# Rover_v1_Overall.net
KiCad netlist of a schematic drawn in EAGLE
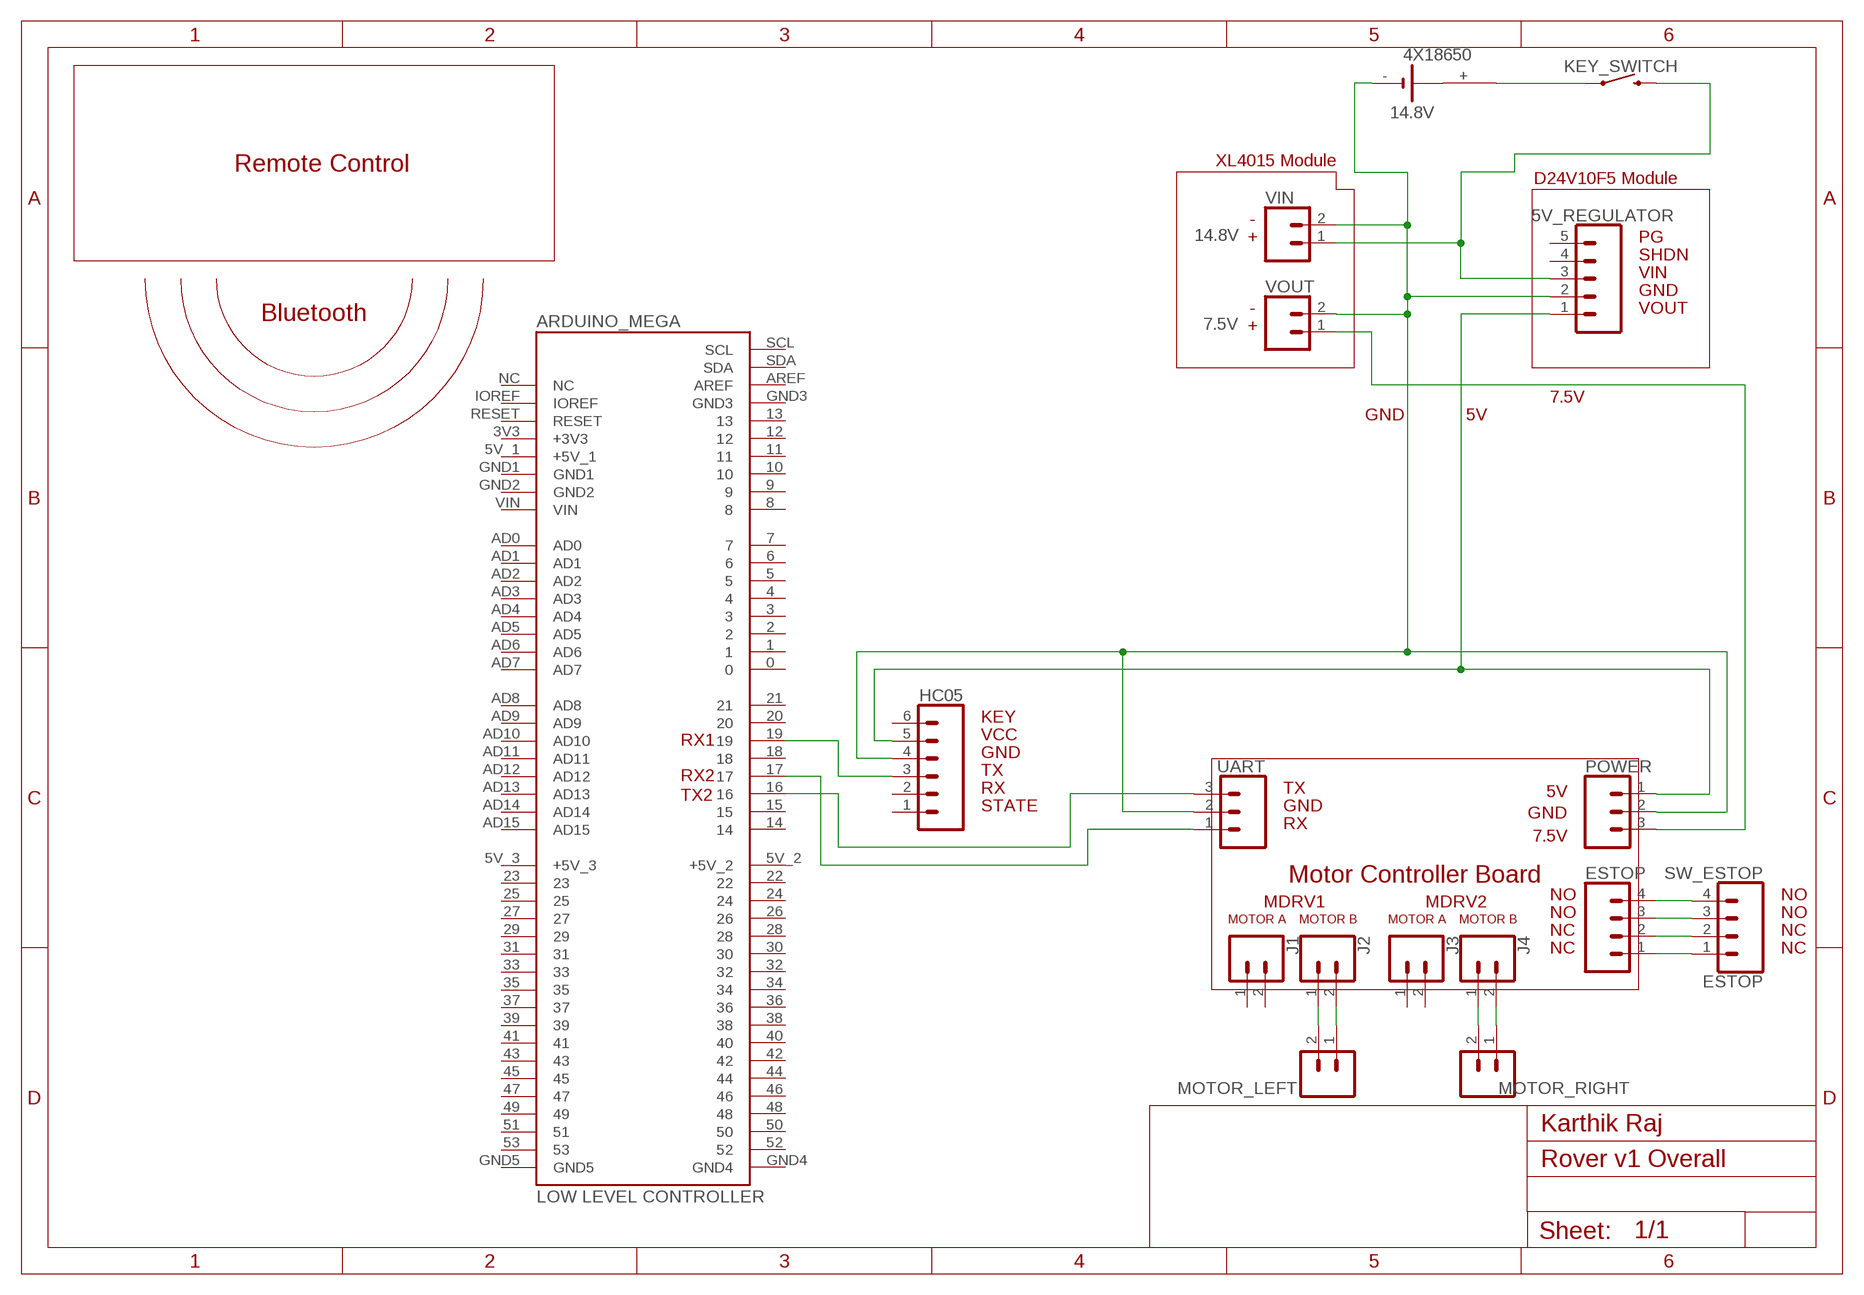
[diagram p0: schematic, sheet 1]

(export (version "E")
  (design (tool "Eeschema 10.0.6"))
  (components
    (comp (ref "4X18650")
      (value "14.8V")
      (footprint "eagle-import:B2430UNI")
      (libsource (lib "eagle-import") (part "B2430UNI"))
    )
    (comp (ref "5V_REGULATOR")
      (value "CONN_05")
      (footprint "eagle-import:1X05")
      (libsource (lib "eagle-import") (part "CONN_05"))
    )
    (comp (ref "ARDUINO_MEGA")
      (value "LOW LEVEL CONTROLLER")
      (footprint "eagle-import:ARDUINO_A000067")
      (fields (field (name "MF") "Arduino") (field (name "MP") "A000067"))
      (libsource (lib "eagle-import") (part "A000067"))
    )
    (comp (ref "ESTOP")
      (value "CONN_04PTH")
      (footprint "eagle-import:1X04")
      (libsource (lib "eagle-import") (part "CONN_04PTH"))
    )
    (comp (ref "HC05")
      (value "CONN_06SILK_FEMALE_PTH")
      (footprint "eagle-import:1X06")
      (libsource (lib "eagle-import") (part "CONN_06SILK_FEMALE_PTH"))
    )
    (comp (ref "J1")
      (value "CONN_02")
      (footprint "eagle-import:1X02")
      (libsource (lib "eagle-import") (part "CONN_02"))
    )
    (comp (ref "J2")
      (value "CONN_02")
      (footprint "eagle-import:1X02")
      (libsource (lib "eagle-import") (part "CONN_02"))
    )
    (comp (ref "J3")
      (value "CONN_02")
      (footprint "eagle-import:1X02")
      (libsource (lib "eagle-import") (part "CONN_02"))
    )
    (comp (ref "J4")
      (value "CONN_02")
      (footprint "eagle-import:1X02")
      (libsource (lib "eagle-import") (part "CONN_02"))
    )
    (comp (ref "KEY_SWITCH")
      (value "MOMENTARY-SWITCH-SPST-PTH-6.0MM")
      (footprint "eagle-import:TACTILE_SWITCH_PTH_6.0MM")
      (libsource (lib "eagle-import") (part "MOMENTARY-SWITCH-SPST-PTH-6.0MM"))
    )
    (comp (ref "MOTOR_LEFT")
      (value "CONN_02")
      (footprint "eagle-import:1X02")
      (libsource (lib "eagle-import") (part "CONN_02"))
    )
    (comp (ref "MOTOR_RIGHT")
      (value "CONN_02")
      (footprint "eagle-import:1X02")
      (libsource (lib "eagle-import") (part "CONN_02"))
    )
    (comp (ref "POWER")
      (value "CONN_03")
      (footprint "eagle-import:1X03")
      (libsource (lib "eagle-import") (part "CONN_03"))
    )
    (comp (ref "SW_ESTOP")
      (value "ESTOP")
      (footprint "eagle-import:1X04")
      (libsource (lib "eagle-import") (part "CONN_04PTH"))
    )
    (comp (ref "UART")
      (value "CONN_03")
      (footprint "eagle-import:1X03")
      (libsource (lib "eagle-import") (part "CONN_03"))
    )
    (comp (ref "VIN")
      (value "14.8V")
      (footprint "eagle-import:1X02")
      (libsource (lib "eagle-import") (part "CONN_02"))
    )
    (comp (ref "VOUT")
      (value "7.5V")
      (footprint "eagle-import:1X02")
      (libsource (lib "eagle-import") (part "CONN_02"))
    )
  )
  (nets
    (net (code "1") (name "Net-(4X18650-Pad+)") (class "Default")
      (node (ref "4X18650") (pin "+") (pinfunction "+_+") (pintype "passive"))
      (node (ref "KEY_SWITCH") (pin "1") (pinfunction "1_1") (pintype "passive"))
    )
    (net (code "2") (name "Net-(4X18650-Pad-)") (class "Default")
      (node (ref "4X18650") (pin "-") (pinfunction "-_-") (pintype "passive"))
      (node (ref "5V_REGULATOR") (pin "2") (pinfunction "2_2") (pintype "passive"))
      (node (ref "HC05") (pin "4") (pinfunction "4_4") (pintype "passive"))
      (node (ref "POWER") (pin "2") (pinfunction "2_2") (pintype "passive"))
      (node (ref "UART") (pin "2") (pinfunction "2_2") (pintype "passive"))
      (node (ref "VIN") (pin "2") (pinfunction "2_2") (pintype "passive"))
      (node (ref "VOUT") (pin "2") (pinfunction "2_2") (pintype "passive"))
    )
    (net (code "3") (name "Net-(5V_REGULATOR-Pad1)") (class "Default")
      (node (ref "5V_REGULATOR") (pin "1") (pinfunction "1_1") (pintype "passive"))
      (node (ref "HC05") (pin "5") (pinfunction "5_5") (pintype "passive"))
      (node (ref "POWER") (pin "1") (pinfunction "1_1") (pintype "passive"))
    )
    (net (code "4") (name "Net-(ARDUINO_MEGA-Pad16)") (class "Default")
      (node (ref "ARDUINO_MEGA") (pin "16") (pinfunction "16_16") (pintype "passive"))
      (node (ref "UART") (pin "3") (pinfunction "3_3") (pintype "passive"))
    )
    (net (code "5") (name "Net-(ARDUINO_MEGA-Pad17)") (class "Default")
      (node (ref "ARDUINO_MEGA") (pin "17") (pinfunction "17_17") (pintype "passive"))
      (node (ref "UART") (pin "1") (pinfunction "1_1") (pintype "passive"))
    )
    (net (code "6") (name "Net-(ARDUINO_MEGA-Pad19)") (class "Default")
      (node (ref "ARDUINO_MEGA") (pin "19") (pinfunction "19_19") (pintype "passive"))
      (node (ref "HC05") (pin "3") (pinfunction "3_3") (pintype "passive"))
    )
    (net (code "7") (name "Net-(ESTOP-Pad1)") (class "Default")
      (node (ref "ESTOP") (pin "1") (pinfunction "1_1") (pintype "passive"))
      (node (ref "SW_ESTOP") (pin "1") (pinfunction "1_1") (pintype "passive"))
    )
    (net (code "8") (name "Net-(ESTOP-Pad2)") (class "Default")
      (node (ref "ESTOP") (pin "2") (pinfunction "2_2") (pintype "passive"))
      (node (ref "SW_ESTOP") (pin "2") (pinfunction "2_2") (pintype "passive"))
    )
    (net (code "9") (name "Net-(ESTOP-Pad3)") (class "Default")
      (node (ref "ESTOP") (pin "3") (pinfunction "3_3") (pintype "passive"))
      (node (ref "SW_ESTOP") (pin "3") (pinfunction "3_3") (pintype "passive"))
    )
    (net (code "10") (name "Net-(ESTOP-Pad4)") (class "Default")
      (node (ref "ESTOP") (pin "4") (pinfunction "4_4") (pintype "passive"))
      (node (ref "SW_ESTOP") (pin "4") (pinfunction "4_4") (pintype "passive"))
    )
    (net (code "11") (name "Net-(J2-Pad1)") (class "Default")
      (node (ref "J2") (pin "1") (pinfunction "1_1") (pintype "passive"))
      (node (ref "MOTOR_LEFT") (pin "2") (pinfunction "2_2") (pintype "passive"))
    )
    (net (code "12") (name "Net-(J2-Pad2)") (class "Default")
      (node (ref "J2") (pin "2") (pinfunction "2_2") (pintype "passive"))
      (node (ref "MOTOR_LEFT") (pin "1") (pinfunction "1_1") (pintype "passive"))
    )
    (net (code "13") (name "Net-(J4-Pad1)") (class "Default")
      (node (ref "J4") (pin "1") (pinfunction "1_1") (pintype "passive"))
      (node (ref "MOTOR_RIGHT") (pin "2") (pinfunction "2_2") (pintype "passive"))
    )
    (net (code "14") (name "Net-(J4-Pad2)") (class "Default")
      (node (ref "J4") (pin "2") (pinfunction "2_2") (pintype "passive"))
      (node (ref "MOTOR_RIGHT") (pin "1") (pinfunction "1_1") (pintype "passive"))
    )
    (net (code "15") (name "Net-(KEY_SWITCH-2)") (class "Default")
      (node (ref "5V_REGULATOR") (pin "3") (pinfunction "3_3") (pintype "passive"))
      (node (ref "KEY_SWITCH") (pin "3") (pinfunction "2_3") (pintype "passive"))
      (node (ref "VIN") (pin "1") (pinfunction "1_1") (pintype "passive"))
    )
    (net (code "16") (name "Net-(POWER-Pad3)") (class "Default")
      (node (ref "POWER") (pin "3") (pinfunction "3_3") (pintype "passive"))
      (node (ref "VOUT") (pin "1") (pinfunction "1_1") (pintype "passive"))
    )
    (net (code "17") (name "unconnected-(4X18650-+-Pad+@1)") (class "Default")
      (node (ref "4X18650") (pin "+@1") (pinfunction "+_+@1") (pintype "passive"))
    )
    (net (code "18") (name "unconnected-(4X18650-+-Pad+@2)") (class "Default")
      (node (ref "4X18650") (pin "+@2") (pinfunction "+_+@2") (pintype "passive"))
    )
    (net (code "19") (name "unconnected-(4X18650-+-Pad+@3)") (class "Default")
      (node (ref "4X18650") (pin "+@3") (pinfunction "+_+@3") (pintype "passive"))
    )
    (net (code "20") (name "unconnected-(4X18650-+-Pad+@4)") (class "Default")
      (node (ref "4X18650") (pin "+@4") (pinfunction "+_+@4") (pintype "passive"))
    )
    (net (code "21") (name "unconnected-(4X18650---Pad-@1)") (class "Default")
      (node (ref "4X18650") (pin "-@1") (pinfunction "-_-@1") (pintype "passive"))
    )
    (net (code "22") (name "unconnected-(5V_REGULATOR-Pad4)") (class "Default")
      (node (ref "5V_REGULATOR") (pin "4") (pinfunction "4_4") (pintype "passive"))
    )
    (net (code "23") (name "unconnected-(5V_REGULATOR-Pad5)") (class "Default")
      (node (ref "5V_REGULATOR") (pin "5") (pinfunction "5_5") (pintype "passive"))
    )
    (net (code "24") (name "unconnected-(ARDUINO_MEGA-+3V3-Pad3V3)") (class "Default")
      (node (ref "ARDUINO_MEGA") (pin "3V3") (pinfunction "+3V3_3V3") (pintype "passive"))
    )
    (net (code "25") (name "unconnected-(ARDUINO_MEGA-+5V_1-Pad5V_1)") (class "Default")
      (node (ref "ARDUINO_MEGA") (pin "5V_1") (pinfunction "+5V_1_5V_1") (pintype "passive"))
    )
    (net (code "26") (name "unconnected-(ARDUINO_MEGA-+5V_2-Pad5V_2)") (class "Default")
      (node (ref "ARDUINO_MEGA") (pin "5V_2") (pinfunction "+5V_2_5V_2") (pintype "passive"))
    )
    (net (code "27") (name "unconnected-(ARDUINO_MEGA-+5V_3-Pad5V_3)") (class "Default")
      (node (ref "ARDUINO_MEGA") (pin "5V_3") (pinfunction "+5V_3_5V_3") (pintype "passive"))
    )
    (net (code "28") (name "unconnected-(ARDUINO_MEGA-Pad0)") (class "Default")
      (node (ref "ARDUINO_MEGA") (pin "0") (pinfunction "0_0") (pintype "passive"))
    )
    (net (code "29") (name "unconnected-(ARDUINO_MEGA-Pad1)") (class "Default")
      (node (ref "ARDUINO_MEGA") (pin "1") (pinfunction "1_1") (pintype "passive"))
    )
    (net (code "30") (name "unconnected-(ARDUINO_MEGA-Pad2)") (class "Default")
      (node (ref "ARDUINO_MEGA") (pin "2") (pinfunction "2_2") (pintype "passive"))
    )
    (net (code "31") (name "unconnected-(ARDUINO_MEGA-Pad3)") (class "Default")
      (node (ref "ARDUINO_MEGA") (pin "3") (pinfunction "3_3") (pintype "passive"))
    )
    (net (code "32") (name "unconnected-(ARDUINO_MEGA-Pad4)") (class "Default")
      (node (ref "ARDUINO_MEGA") (pin "4") (pinfunction "4_4") (pintype "passive"))
    )
    (net (code "33") (name "unconnected-(ARDUINO_MEGA-Pad5)") (class "Default")
      (node (ref "ARDUINO_MEGA") (pin "5") (pinfunction "5_5") (pintype "passive"))
    )
    (net (code "34") (name "unconnected-(ARDUINO_MEGA-Pad6)") (class "Default")
      (node (ref "ARDUINO_MEGA") (pin "6") (pinfunction "6_6") (pintype "passive"))
    )
    (net (code "35") (name "unconnected-(ARDUINO_MEGA-Pad7)") (class "Default")
      (node (ref "ARDUINO_MEGA") (pin "7") (pinfunction "7_7") (pintype "passive"))
    )
    (net (code "36") (name "unconnected-(ARDUINO_MEGA-Pad8)") (class "Default")
      (node (ref "ARDUINO_MEGA") (pin "8") (pinfunction "8_8") (pintype "passive"))
    )
    (net (code "37") (name "unconnected-(ARDUINO_MEGA-Pad9)") (class "Default")
      (node (ref "ARDUINO_MEGA") (pin "9") (pinfunction "9_9") (pintype "passive"))
    )
    (net (code "38") (name "unconnected-(ARDUINO_MEGA-Pad10)") (class "Default")
      (node (ref "ARDUINO_MEGA") (pin "10") (pinfunction "10_10") (pintype "passive"))
    )
    (net (code "39") (name "unconnected-(ARDUINO_MEGA-Pad11)") (class "Default")
      (node (ref "ARDUINO_MEGA") (pin "11") (pinfunction "11_11") (pintype "passive"))
    )
    (net (code "40") (name "unconnected-(ARDUINO_MEGA-Pad12)") (class "Default")
      (node (ref "ARDUINO_MEGA") (pin "12") (pinfunction "12_12") (pintype "passive"))
    )
    (net (code "41") (name "unconnected-(ARDUINO_MEGA-Pad13)") (class "Default")
      (node (ref "ARDUINO_MEGA") (pin "13") (pinfunction "13_13") (pintype "passive"))
    )
    (net (code "42") (name "unconnected-(ARDUINO_MEGA-Pad14)") (class "Default")
      (node (ref "ARDUINO_MEGA") (pin "14") (pinfunction "14_14") (pintype "passive"))
    )
    (net (code "43") (name "unconnected-(ARDUINO_MEGA-Pad15)") (class "Default")
      (node (ref "ARDUINO_MEGA") (pin "15") (pinfunction "15_15") (pintype "passive"))
    )
    (net (code "44") (name "unconnected-(ARDUINO_MEGA-Pad18)") (class "Default")
      (node (ref "ARDUINO_MEGA") (pin "18") (pinfunction "18_18") (pintype "passive"))
    )
    (net (code "45") (name "unconnected-(ARDUINO_MEGA-Pad20)") (class "Default")
      (node (ref "ARDUINO_MEGA") (pin "20") (pinfunction "20_20") (pintype "passive"))
    )
    (net (code "46") (name "unconnected-(ARDUINO_MEGA-Pad21)") (class "Default")
      (node (ref "ARDUINO_MEGA") (pin "21") (pinfunction "21_21") (pintype "passive"))
    )
    (net (code "47") (name "unconnected-(ARDUINO_MEGA-Pad22)") (class "Default")
      (node (ref "ARDUINO_MEGA") (pin "22") (pinfunction "22_22") (pintype "passive"))
    )
    (net (code "48") (name "unconnected-(ARDUINO_MEGA-Pad23)") (class "Default")
      (node (ref "ARDUINO_MEGA") (pin "23") (pinfunction "23_23") (pintype "passive"))
    )
    (net (code "49") (name "unconnected-(ARDUINO_MEGA-Pad24)") (class "Default")
      (node (ref "ARDUINO_MEGA") (pin "24") (pinfunction "24_24") (pintype "passive"))
    )
    (net (code "50") (name "unconnected-(ARDUINO_MEGA-Pad25)") (class "Default")
      (node (ref "ARDUINO_MEGA") (pin "25") (pinfunction "25_25") (pintype "passive"))
    )
    (net (code "51") (name "unconnected-(ARDUINO_MEGA-Pad26)") (class "Default")
      (node (ref "ARDUINO_MEGA") (pin "26") (pinfunction "26_26") (pintype "passive"))
    )
    (net (code "52") (name "unconnected-(ARDUINO_MEGA-Pad27)") (class "Default")
      (node (ref "ARDUINO_MEGA") (pin "27") (pinfunction "27_27") (pintype "passive"))
    )
    (net (code "53") (name "unconnected-(ARDUINO_MEGA-Pad28)") (class "Default")
      (node (ref "ARDUINO_MEGA") (pin "28") (pinfunction "28_28") (pintype "passive"))
    )
    (net (code "54") (name "unconnected-(ARDUINO_MEGA-Pad29)") (class "Default")
      (node (ref "ARDUINO_MEGA") (pin "29") (pinfunction "29_29") (pintype "passive"))
    )
    (net (code "55") (name "unconnected-(ARDUINO_MEGA-Pad30)") (class "Default")
      (node (ref "ARDUINO_MEGA") (pin "30") (pinfunction "30_30") (pintype "passive"))
    )
    (net (code "56") (name "unconnected-(ARDUINO_MEGA-Pad31)") (class "Default")
      (node (ref "ARDUINO_MEGA") (pin "31") (pinfunction "31_31") (pintype "passive"))
    )
    (net (code "57") (name "unconnected-(ARDUINO_MEGA-Pad32)") (class "Default")
      (node (ref "ARDUINO_MEGA") (pin "32") (pinfunction "32_32") (pintype "passive"))
    )
    (net (code "58") (name "unconnected-(ARDUINO_MEGA-Pad33)") (class "Default")
      (node (ref "ARDUINO_MEGA") (pin "33") (pinfunction "33_33") (pintype "passive"))
    )
    (net (code "59") (name "unconnected-(ARDUINO_MEGA-Pad34)") (class "Default")
      (node (ref "ARDUINO_MEGA") (pin "34") (pinfunction "34_34") (pintype "passive"))
    )
    (net (code "60") (name "unconnected-(ARDUINO_MEGA-Pad35)") (class "Default")
      (node (ref "ARDUINO_MEGA") (pin "35") (pinfunction "35_35") (pintype "passive"))
    )
    (net (code "61") (name "unconnected-(ARDUINO_MEGA-Pad36)") (class "Default")
      (node (ref "ARDUINO_MEGA") (pin "36") (pinfunction "36_36") (pintype "passive"))
    )
    (net (code "62") (name "unconnected-(ARDUINO_MEGA-Pad37)") (class "Default")
      (node (ref "ARDUINO_MEGA") (pin "37") (pinfunction "37_37") (pintype "passive"))
    )
    (net (code "63") (name "unconnected-(ARDUINO_MEGA-Pad38)") (class "Default")
      (node (ref "ARDUINO_MEGA") (pin "38") (pinfunction "38_38") (pintype "passive"))
    )
    (net (code "64") (name "unconnected-(ARDUINO_MEGA-Pad39)") (class "Default")
      (node (ref "ARDUINO_MEGA") (pin "39") (pinfunction "39_39") (pintype "passive"))
    )
    (net (code "65") (name "unconnected-(ARDUINO_MEGA-Pad40)") (class "Default")
      (node (ref "ARDUINO_MEGA") (pin "40") (pinfunction "40_40") (pintype "passive"))
    )
    (net (code "66") (name "unconnected-(ARDUINO_MEGA-Pad41)") (class "Default")
      (node (ref "ARDUINO_MEGA") (pin "41") (pinfunction "41_41") (pintype "passive"))
    )
    (net (code "67") (name "unconnected-(ARDUINO_MEGA-Pad42)") (class "Default")
      (node (ref "ARDUINO_MEGA") (pin "42") (pinfunction "42_42") (pintype "passive"))
    )
    (net (code "68") (name "unconnected-(ARDUINO_MEGA-Pad43)") (class "Default")
      (node (ref "ARDUINO_MEGA") (pin "43") (pinfunction "43_43") (pintype "passive"))
    )
    (net (code "69") (name "unconnected-(ARDUINO_MEGA-Pad44)") (class "Default")
      (node (ref "ARDUINO_MEGA") (pin "44") (pinfunction "44_44") (pintype "passive"))
    )
    (net (code "70") (name "unconnected-(ARDUINO_MEGA-Pad45)") (class "Default")
      (node (ref "ARDUINO_MEGA") (pin "45") (pinfunction "45_45") (pintype "passive"))
    )
    (net (code "71") (name "unconnected-(ARDUINO_MEGA-Pad46)") (class "Default")
      (node (ref "ARDUINO_MEGA") (pin "46") (pinfunction "46_46") (pintype "passive"))
    )
    (net (code "72") (name "unconnected-(ARDUINO_MEGA-Pad47)") (class "Default")
      (node (ref "ARDUINO_MEGA") (pin "47") (pinfunction "47_47") (pintype "passive"))
    )
    (net (code "73") (name "unconnected-(ARDUINO_MEGA-Pad48)") (class "Default")
      (node (ref "ARDUINO_MEGA") (pin "48") (pinfunction "48_48") (pintype "passive"))
    )
    (net (code "74") (name "unconnected-(ARDUINO_MEGA-Pad49)") (class "Default")
      (node (ref "ARDUINO_MEGA") (pin "49") (pinfunction "49_49") (pintype "passive"))
    )
    (net (code "75") (name "unconnected-(ARDUINO_MEGA-Pad50)") (class "Default")
      (node (ref "ARDUINO_MEGA") (pin "50") (pinfunction "50_50") (pintype "passive"))
    )
    (net (code "76") (name "unconnected-(ARDUINO_MEGA-Pad51)") (class "Default")
      (node (ref "ARDUINO_MEGA") (pin "51") (pinfunction "51_51") (pintype "passive"))
    )
    (net (code "77") (name "unconnected-(ARDUINO_MEGA-Pad52)") (class "Default")
      (node (ref "ARDUINO_MEGA") (pin "52") (pinfunction "52_52") (pintype "passive"))
    )
    (net (code "78") (name "unconnected-(ARDUINO_MEGA-Pad53)") (class "Default")
      (node (ref "ARDUINO_MEGA") (pin "53") (pinfunction "53_53") (pintype "passive"))
    )
    (net (code "79") (name "unconnected-(ARDUINO_MEGA-PadAD0)") (class "Default")
      (node (ref "ARDUINO_MEGA") (pin "AD0") (pinfunction "AD0_AD0") (pintype "passive"))
    )
    (net (code "80") (name "unconnected-(ARDUINO_MEGA-PadAD1)") (class "Default")
      (node (ref "ARDUINO_MEGA") (pin "AD1") (pinfunction "AD1_AD1") (pintype "passive"))
    )
    (net (code "81") (name "unconnected-(ARDUINO_MEGA-PadAD2)") (class "Default")
      (node (ref "ARDUINO_MEGA") (pin "AD2") (pinfunction "AD2_AD2") (pintype "passive"))
    )
    (net (code "82") (name "unconnected-(ARDUINO_MEGA-PadAD3)") (class "Default")
      (node (ref "ARDUINO_MEGA") (pin "AD3") (pinfunction "AD3_AD3") (pintype "passive"))
    )
    (net (code "83") (name "unconnected-(ARDUINO_MEGA-PadAD4)") (class "Default")
      (node (ref "ARDUINO_MEGA") (pin "AD4") (pinfunction "AD4_AD4") (pintype "passive"))
    )
    (net (code "84") (name "unconnected-(ARDUINO_MEGA-PadAD5)") (class "Default")
      (node (ref "ARDUINO_MEGA") (pin "AD5") (pinfunction "AD5_AD5") (pintype "passive"))
    )
    (net (code "85") (name "unconnected-(ARDUINO_MEGA-PadAD6)") (class "Default")
      (node (ref "ARDUINO_MEGA") (pin "AD6") (pinfunction "AD6_AD6") (pintype "passive"))
    )
    (net (code "86") (name "unconnected-(ARDUINO_MEGA-PadAD7)") (class "Default")
      (node (ref "ARDUINO_MEGA") (pin "AD7") (pinfunction "AD7_AD7") (pintype "passive"))
    )
    (net (code "87") (name "unconnected-(ARDUINO_MEGA-PadAD8)") (class "Default")
      (node (ref "ARDUINO_MEGA") (pin "AD8") (pinfunction "AD8_AD8") (pintype "passive"))
    )
    (net (code "88") (name "unconnected-(ARDUINO_MEGA-PadAD9)") (class "Default")
      (node (ref "ARDUINO_MEGA") (pin "AD9") (pinfunction "AD9_AD9") (pintype "passive"))
    )
    (net (code "89") (name "unconnected-(ARDUINO_MEGA-PadAD10)") (class "Default")
      (node (ref "ARDUINO_MEGA") (pin "AD10") (pinfunction "AD10_AD10") (pintype "passive"))
    )
    (net (code "90") (name "unconnected-(ARDUINO_MEGA-PadAD11)") (class "Default")
      (node (ref "ARDUINO_MEGA") (pin "AD11") (pinfunction "AD11_AD11") (pintype "passive"))
    )
    (net (code "91") (name "unconnected-(ARDUINO_MEGA-PadAD12)") (class "Default")
      (node (ref "ARDUINO_MEGA") (pin "AD12") (pinfunction "AD12_AD12") (pintype "passive"))
    )
    (net (code "92") (name "unconnected-(ARDUINO_MEGA-PadAD13)") (class "Default")
      (node (ref "ARDUINO_MEGA") (pin "AD13") (pinfunction "AD13_AD13") (pintype "passive"))
    )
    (net (code "93") (name "unconnected-(ARDUINO_MEGA-PadAD14)") (class "Default")
      (node (ref "ARDUINO_MEGA") (pin "AD14") (pinfunction "AD14_AD14") (pintype "passive"))
    )
    (net (code "94") (name "unconnected-(ARDUINO_MEGA-PadAD15)") (class "Default")
      (node (ref "ARDUINO_MEGA") (pin "AD15") (pinfunction "AD15_AD15") (pintype "passive"))
    )
    (net (code "95") (name "unconnected-(ARDUINO_MEGA-PadAREF)") (class "Default")
      (node (ref "ARDUINO_MEGA") (pin "AREF") (pinfunction "AREF_AREF") (pintype "passive"))
    )
    (net (code "96") (name "unconnected-(ARDUINO_MEGA-PadGND1)") (class "Default")
      (node (ref "ARDUINO_MEGA") (pin "GND1") (pinfunction "GND1_GND1") (pintype "passive"))
    )
    (net (code "97") (name "unconnected-(ARDUINO_MEGA-PadGND2)") (class "Default")
      (node (ref "ARDUINO_MEGA") (pin "GND2") (pinfunction "GND2_GND2") (pintype "passive"))
    )
    (net (code "98") (name "unconnected-(ARDUINO_MEGA-PadGND3)") (class "Default")
      (node (ref "ARDUINO_MEGA") (pin "GND3") (pinfunction "GND3_GND3") (pintype "passive"))
    )
    (net (code "99") (name "unconnected-(ARDUINO_MEGA-PadGND4)") (class "Default")
      (node (ref "ARDUINO_MEGA") (pin "GND4") (pinfunction "GND4_GND4") (pintype "passive"))
    )
    (net (code "100") (name "unconnected-(ARDUINO_MEGA-PadGND5)") (class "Default")
      (node (ref "ARDUINO_MEGA") (pin "GND5") (pinfunction "GND5_GND5") (pintype "passive"))
    )
    (net (code "101") (name "unconnected-(ARDUINO_MEGA-PadIOREF)") (class "Default")
      (node (ref "ARDUINO_MEGA") (pin "IOREF") (pinfunction "IOREF_IOREF") (pintype "passive"))
    )
    (net (code "102") (name "unconnected-(ARDUINO_MEGA-PadNC)") (class "Default")
      (node (ref "ARDUINO_MEGA") (pin "NC") (pinfunction "NC_NC") (pintype "passive"))
    )
    (net (code "103") (name "unconnected-(ARDUINO_MEGA-PadRESET)") (class "Default")
      (node (ref "ARDUINO_MEGA") (pin "RESET") (pinfunction "RESET_RESET") (pintype "passive"))
    )
    (net (code "104") (name "unconnected-(ARDUINO_MEGA-PadSCL)") (class "Default")
      (node (ref "ARDUINO_MEGA") (pin "SCL") (pinfunction "SCL_SCL") (pintype "passive"))
    )
    (net (code "105") (name "unconnected-(ARDUINO_MEGA-PadSDA)") (class "Default")
      (node (ref "ARDUINO_MEGA") (pin "SDA") (pinfunction "SDA_SDA") (pintype "passive"))
    )
    (net (code "106") (name "unconnected-(ARDUINO_MEGA-PadVIN)") (class "Default")
      (node (ref "ARDUINO_MEGA") (pin "VIN") (pinfunction "VIN_VIN") (pintype "passive"))
    )
    (net (code "107") (name "unconnected-(HC05-Pad1)") (class "Default")
      (node (ref "HC05") (pin "1") (pinfunction "1_1") (pintype "passive"))
    )
    (net (code "108") (name "unconnected-(HC05-Pad2)") (class "Default")
      (node (ref "HC05") (pin "2") (pinfunction "2_2") (pintype "passive"))
    )
    (net (code "109") (name "unconnected-(HC05-Pad6)") (class "Default")
      (node (ref "HC05") (pin "6") (pinfunction "6_6") (pintype "passive"))
    )
    (net (code "110") (name "unconnected-(J1-Pad1)") (class "Default")
      (node (ref "J1") (pin "1") (pinfunction "1_1") (pintype "passive"))
    )
    (net (code "111") (name "unconnected-(J1-Pad2)") (class "Default")
      (node (ref "J1") (pin "2") (pinfunction "2_2") (pintype "passive"))
    )
    (net (code "112") (name "unconnected-(J3-Pad1)") (class "Default")
      (node (ref "J3") (pin "1") (pinfunction "1_1") (pintype "passive"))
    )
    (net (code "113") (name "unconnected-(J3-Pad2)") (class "Default")
      (node (ref "J3") (pin "2") (pinfunction "2_2") (pintype "passive"))
    )
  )
)
